# Adafruit_NeoRGB_Stemma_Rev_B.net
KiCad netlist of a schematic drawn in EAGLE
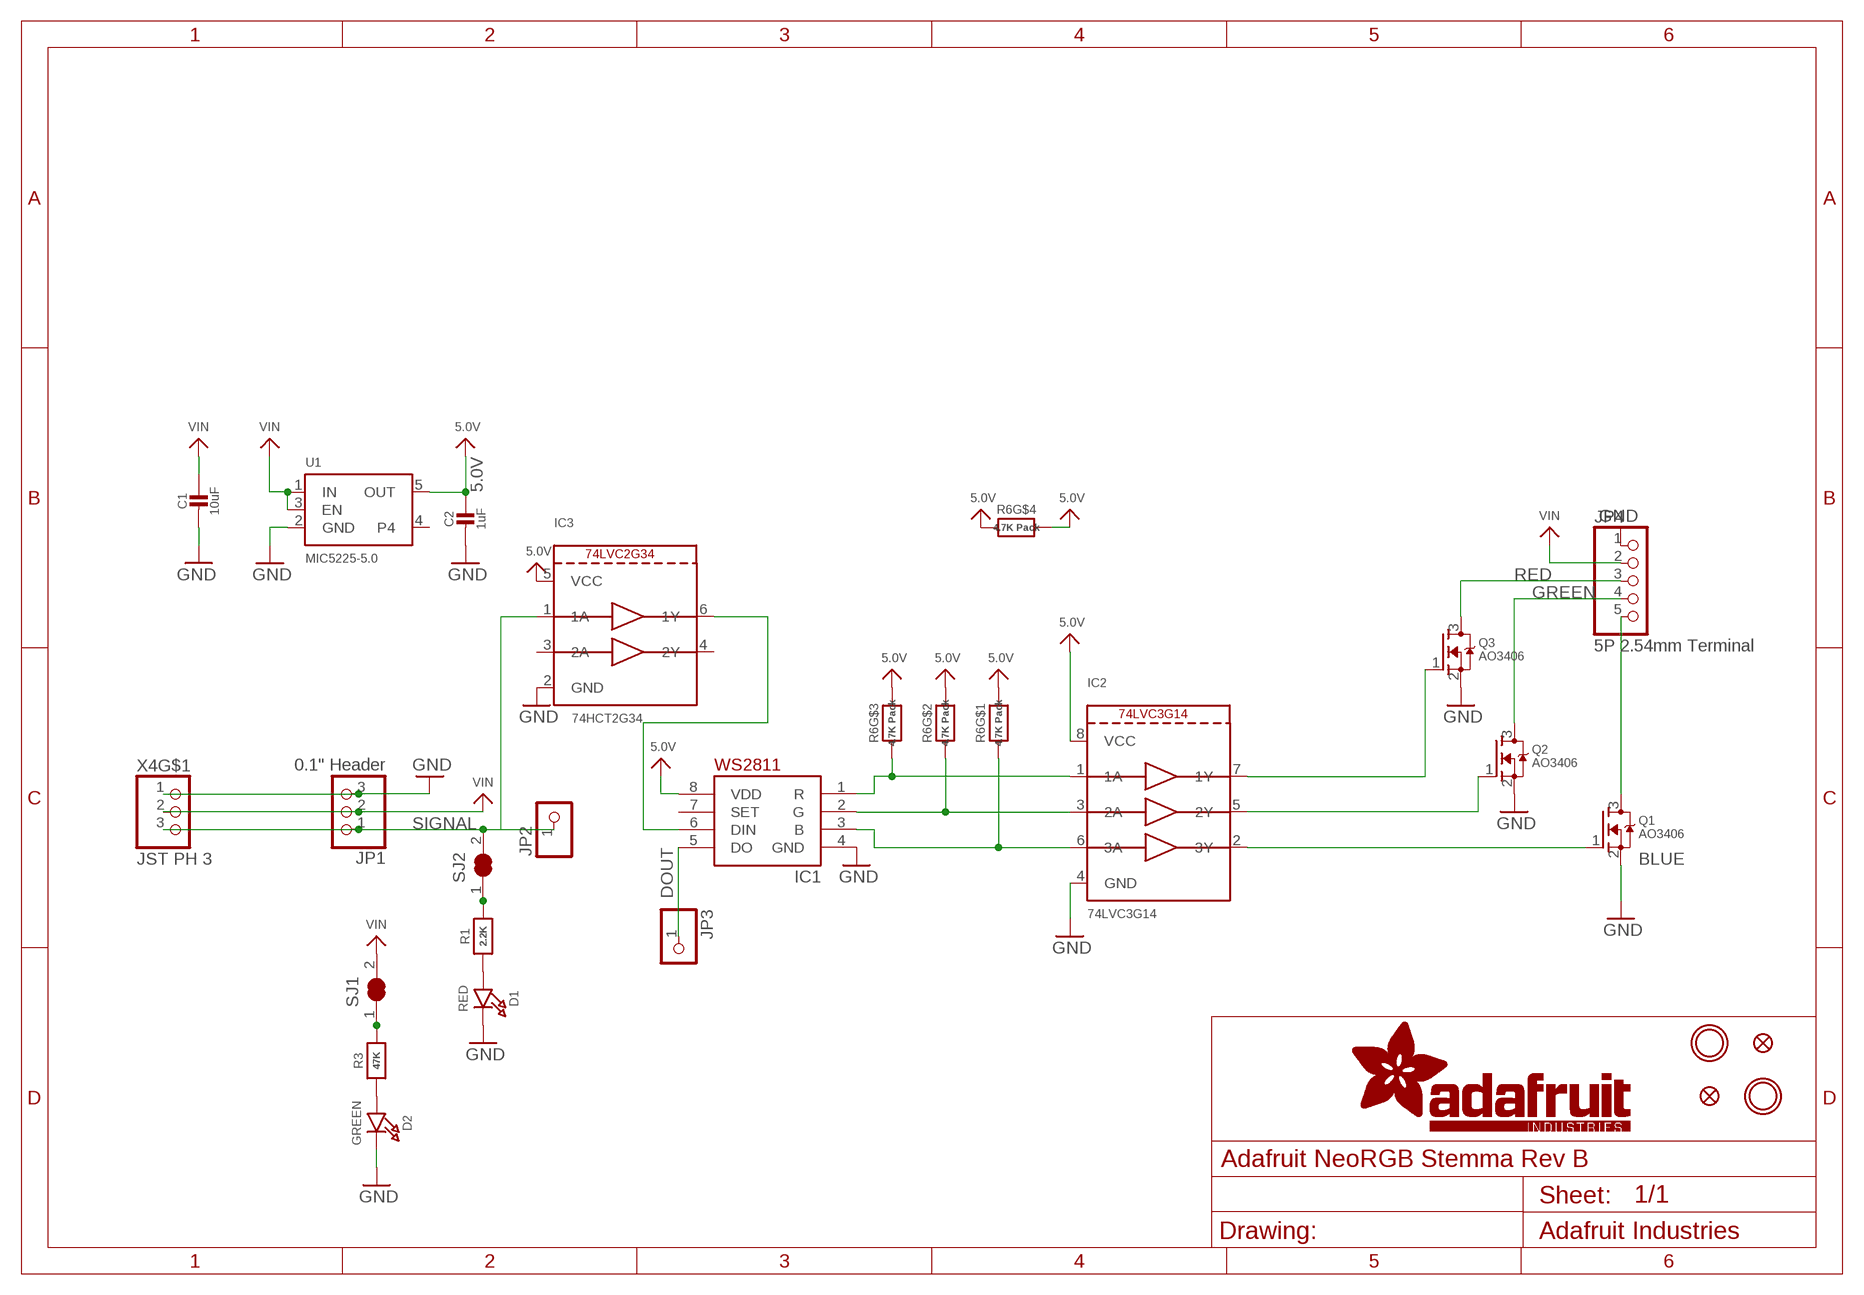
[diagram p0: schematic, sheet 1]

(export (version "E")
  (design (tool "Eeschema 10.0.6"))
  (components
    (comp (ref "C1")
      (value "10uF")
      (footprint "eagle-import:0805-NO")
      (libsource (lib "eagle-import") (part "CAP_CERAMIC0805-NOOUTLINE"))
    )
    (comp (ref "C2")
      (value "1uF")
      (footprint "eagle-import:0603-NO")
      (libsource (lib "eagle-import") (part "CAP_CERAMIC0603_NO"))
    )
    (comp (ref "D1")
      (value "RED")
      (footprint "eagle-import:CHIPLED_0603_NOOUTLINE")
      (libsource (lib "eagle-import") (part "LED0603_NOOUTLINE"))
    )
    (comp (ref "D2")
      (value "GREEN")
      (footprint "eagle-import:CHIPLED_0603_NOOUTLINE")
      (libsource (lib "eagle-import") (part "LED0603_NOOUTLINE"))
    )
    (comp (ref "FID2")
      (value "FIDUCIAL_1MM")
      (footprint "eagle-import:FIDUCIAL_1MM")
      (libsource (lib "eagle-import") (part "FIDUCIAL_1MM"))
    )
    (comp (ref "FID3")
      (value "FIDUCIAL_1MM")
      (footprint "eagle-import:FIDUCIAL_1MM")
      (libsource (lib "eagle-import") (part "FIDUCIAL_1MM"))
    )
    (comp (ref "IC1")
      (value "WS2811F")
      (footprint "eagle-import:FSOP-8")
      (libsource (lib "eagle-import") (part "WS2811F"))
    )
    (comp (ref "IC2")
      (value "74LVC3G14")
      (footprint "eagle-import:VFSOP-8")
      (libsource (lib "eagle-import") (part "74LVC3G14"))
    )
    (comp (ref "IC3")
      (value "74HCT2G34")
      (footprint "eagle-import:SC70-6L")
      (libsource (lib "eagle-import") (part "74LVC2G34"))
    )
    (comp (ref "JP1")
      (value "0.1\" Header")
      (footprint "eagle-import:1X03_OVAL")
      (libsource (lib "eagle-import") (part "HEADER-1X3"))
    )
    (comp (ref "JP2")
      (value "HEADER-1X1ROUND")
      (footprint "eagle-import:1X01_ROUND")
      (libsource (lib "eagle-import") (part "HEADER-1X1ROUND"))
    )
    (comp (ref "JP3")
      (value "HEADER-1X1ROUND")
      (footprint "eagle-import:1X01_ROUND")
      (libsource (lib "eagle-import") (part "HEADER-1X1ROUND"))
    )
    (comp (ref "JP4")
      (value "5P 2.54mm Terminal")
      (footprint "eagle-import:1X05_2.54MMTERMINAL")
      (libsource (lib "eagle-import") (part "HEADER-1X5_2.54MMTERM"))
    )
    (comp (ref "Q1")
      (value "AO3406")
      (footprint "eagle-import:SOT23-WIDE")
      (libsource (lib "eagle-import") (part "MOSFET-NWIDE"))
    )
    (comp (ref "Q2")
      (value "AO3406")
      (footprint "eagle-import:SOT23-WIDE")
      (libsource (lib "eagle-import") (part "MOSFET-NWIDE"))
    )
    (comp (ref "Q3")
      (value "AO3406")
      (footprint "eagle-import:SOT23-WIDE")
      (libsource (lib "eagle-import") (part "MOSFET-NWIDE"))
    )
    (comp (ref "R1")
      (value "2.2K")
      (footprint "eagle-import:0603-NO")
      (libsource (lib "eagle-import") (part "RESISTOR_0603_NOOUT"))
    )
    (comp (ref "R3")
      (value "47K")
      (footprint "eagle-import:0603-NO")
      (libsource (lib "eagle-import") (part "RESISTOR_0603_NOOUT"))
    )
    (comp (ref "R6")
      (value "4.7K Pack")
      (footprint "eagle-import:RESPACK_4X0402")
      (libsource (lib "eagle-import") (part "RESISTOR_4PACK_0804"))
    )
    (comp (ref "SJ1")
      (value "SOLDERJUMPER_CLOSED")
      (footprint "eagle-import:SOLDERJUMPER_CLOSEDWIRE")
      (libsource (lib "eagle-import") (part "SOLDERJUMPER_CLOSED"))
    )
    (comp (ref "SJ2")
      (value "SOLDERJUMPER_CLOSED")
      (footprint "eagle-import:SOLDERJUMPER_CLOSEDWIRE")
      (libsource (lib "eagle-import") (part "SOLDERJUMPER_CLOSED"))
    )
    (comp (ref "U$1")
      (value "MOUNTINGHOLE2.5")
      (footprint "eagle-import:MOUNTINGHOLE_2.5_PLATED")
      (libsource (lib "eagle-import") (part "MOUNTINGHOLE2.5"))
    )
    (comp (ref "U$8")
      (value "MOUNTINGHOLE2.5")
      (footprint "eagle-import:MOUNTINGHOLE_2.5_PLATED")
      (libsource (lib "eagle-import") (part "MOUNTINGHOLE2.5"))
    )
    (comp (ref "U1")
      (value "MIC5225-5.0")
      (footprint "eagle-import:SOT23-5")
      (fields (field (name "JLC_ROTATION") "0"))
      (libsource (lib "eagle-import") (part "VREG_SOT23-5"))
    )
    (comp (ref "X4")
      (value "JST PH 3")
      (footprint "eagle-import:JSTPH3")
      (libsource (lib "eagle-import") (part "CON_JST_PH_3PIN"))
    )
  )
  (nets
    (net (code "1") (name "/BLUE") (class "Default")
      (node (ref "JP4") (pin "5") (pinfunction "5_5") (pintype "passive"))
      (node (ref "Q1") (pin "3") (pinfunction "D_3") (pintype "bidirectional"))
    )
    (net (code "2") (name "/DOUT") (class "Default")
      (node (ref "IC1") (pin "5") (pinfunction "DO_5") (pintype "output"))
      (node (ref "JP3") (pin "1") (pinfunction "1_1") (pintype "passive"))
    )
    (net (code "3") (name "/GREEN") (class "Default")
      (node (ref "JP4") (pin "4") (pinfunction "4_4") (pintype "passive"))
      (node (ref "Q2") (pin "3") (pinfunction "D_3") (pintype "bidirectional"))
    )
    (net (code "4") (name "/RED") (class "Default")
      (node (ref "JP4") (pin "3") (pinfunction "3_3") (pintype "passive"))
      (node (ref "Q3") (pin "3") (pinfunction "D_3") (pintype "bidirectional"))
    )
    (net (code "5") (name "/SIGNAL") (class "Default")
      (node (ref "IC3") (pin "1") (pinfunction "1A_1") (pintype "input"))
      (node (ref "JP1") (pin "1") (pinfunction "1_1") (pintype "passive"))
      (node (ref "JP2") (pin "1") (pinfunction "1_1") (pintype "passive"))
      (node (ref "SJ2") (pin "2") (pinfunction "2_2") (pintype "passive"))
      (node (ref "X4") (pin "3") (pinfunction "3_3") (pintype "passive"))
    )
    (net (code "6") (name "5.0V") (class "Default")
      (node (ref "C2") (pin "1") (pinfunction "1_1") (pintype "passive"))
      (node (ref "IC1") (pin "8") (pinfunction "VDD_8") (pintype "power_in"))
      (node (ref "IC2") (pin "8") (pinfunction "VCC_8") (pintype "power_in"))
      (node (ref "IC3") (pin "5") (pinfunction "VCC_5") (pintype "power_in"))
      (node (ref "R6") (pin "4") (pinfunction "1_4") (pintype "passive"))
      (node (ref "R6") (pin "5") (pinfunction "2_5") (pintype "passive"))
      (node (ref "R6") (pin "6") (pinfunction "2_6") (pintype "passive"))
      (node (ref "R6") (pin "7") (pinfunction "2_7") (pintype "passive"))
      (node (ref "R6") (pin "8") (pinfunction "2_8") (pintype "passive"))
      (node (ref "U1") (pin "5") (pinfunction "OUT_5") (pintype "power_in"))
    )
    (net (code "7") (name "GND") (class "Default")
      (node (ref "C1") (pin "2") (pinfunction "2_2") (pintype "passive"))
      (node (ref "C2") (pin "2") (pinfunction "2_2") (pintype "passive"))
      (node (ref "D1") (pin "C") (pinfunction "C_C") (pintype "passive"))
      (node (ref "D2") (pin "C") (pinfunction "C_C") (pintype "passive"))
      (node (ref "IC1") (pin "4") (pinfunction "GND_4") (pintype "power_in"))
      (node (ref "IC2") (pin "4") (pinfunction "GND_4") (pintype "power_in"))
      (node (ref "IC3") (pin "2") (pinfunction "GND_2") (pintype "power_in"))
      (node (ref "JP1") (pin "3") (pinfunction "3_3") (pintype "passive"))
      (node (ref "JP4") (pin "1") (pinfunction "1_1") (pintype "passive"))
      (node (ref "Q1") (pin "2") (pinfunction "S_2") (pintype "bidirectional"))
      (node (ref "Q2") (pin "2") (pinfunction "S_2") (pintype "bidirectional"))
      (node (ref "Q3") (pin "2") (pinfunction "S_2") (pintype "bidirectional"))
      (node (ref "U1") (pin "2") (pinfunction "GND_2") (pintype "power_in"))
      (node (ref "X4") (pin "1") (pinfunction "1_1") (pintype "passive"))
    )
    (net (code "8") (name "Net-(D1-PadA)") (class "Default")
      (node (ref "D1") (pin "A") (pinfunction "A_A") (pintype "passive"))
      (node (ref "R1") (pin "1") (pinfunction "1_1") (pintype "passive"))
    )
    (net (code "9") (name "Net-(D2-PadA)") (class "Default")
      (node (ref "D2") (pin "A") (pinfunction "A_A") (pintype "passive"))
      (node (ref "R3") (pin "1") (pinfunction "1_1") (pintype "passive"))
    )
    (net (code "10") (name "Net-(IC1-B)") (class "Default")
      (node (ref "IC1") (pin "3") (pinfunction "B_3") (pintype "open_collector"))
      (node (ref "IC2") (pin "6") (pinfunction "3A_6") (pintype "input"))
      (node (ref "R6") (pin "1") (pinfunction "1_1") (pintype "passive"))
    )
    (net (code "11") (name "Net-(IC1-DIN)") (class "Default")
      (node (ref "IC1") (pin "6") (pinfunction "DIN_6") (pintype "input"))
      (node (ref "IC3") (pin "6") (pinfunction "1Y_6") (pintype "output"))
    )
    (net (code "12") (name "Net-(IC1-G)") (class "Default")
      (node (ref "IC1") (pin "2") (pinfunction "G_2") (pintype "open_collector"))
      (node (ref "IC2") (pin "3") (pinfunction "2A_3") (pintype "input"))
      (node (ref "R6") (pin "2") (pinfunction "1_2") (pintype "passive"))
    )
    (net (code "13") (name "Net-(IC1-R)") (class "Default")
      (node (ref "IC1") (pin "1") (pinfunction "R_1") (pintype "open_collector"))
      (node (ref "IC2") (pin "1") (pinfunction "1A_1") (pintype "input"))
      (node (ref "R6") (pin "3") (pinfunction "1_3") (pintype "passive"))
    )
    (net (code "14") (name "Net-(IC2-1Y)") (class "Default")
      (node (ref "IC2") (pin "7") (pinfunction "1Y_7") (pintype "output"))
      (node (ref "Q3") (pin "1") (pinfunction "G_1") (pintype "bidirectional"))
    )
    (net (code "15") (name "Net-(IC2-2Y)") (class "Default")
      (node (ref "IC2") (pin "5") (pinfunction "2Y_5") (pintype "output"))
      (node (ref "Q2") (pin "1") (pinfunction "G_1") (pintype "bidirectional"))
    )
    (net (code "16") (name "Net-(IC2-3Y)") (class "Default")
      (node (ref "IC2") (pin "2") (pinfunction "3Y_2") (pintype "output"))
      (node (ref "Q1") (pin "1") (pinfunction "G_1") (pintype "bidirectional"))
    )
    (net (code "17") (name "Net-(R1-Pad2)") (class "Default")
      (node (ref "R1") (pin "2") (pinfunction "2_2") (pintype "passive"))
      (node (ref "SJ2") (pin "1") (pinfunction "1_1") (pintype "passive"))
    )
    (net (code "18") (name "Net-(R3-Pad2)") (class "Default")
      (node (ref "R3") (pin "2") (pinfunction "2_2") (pintype "passive"))
      (node (ref "SJ1") (pin "1") (pinfunction "1_1") (pintype "passive"))
    )
    (net (code "19") (name "VIN") (class "Default")
      (node (ref "C1") (pin "1") (pinfunction "1_1") (pintype "passive"))
      (node (ref "JP1") (pin "2") (pinfunction "2_2") (pintype "passive"))
      (node (ref "JP4") (pin "2") (pinfunction "2_2") (pintype "passive"))
      (node (ref "SJ1") (pin "2") (pinfunction "2_2") (pintype "passive"))
      (node (ref "U1") (pin "1") (pinfunction "IN_1") (pintype "power_in"))
      (node (ref "U1") (pin "3") (pinfunction "EN_3") (pintype "input"))
      (node (ref "X4") (pin "2") (pinfunction "2_2") (pintype "passive"))
    )
    (net (code "20") (name "unconnected-(IC1-SET-Pad7)") (class "Default")
      (node (ref "IC1") (pin "7") (pinfunction "SET_7") (pintype "input"))
    )
    (net (code "21") (name "unconnected-(IC3-2A-Pad3)") (class "Default")
      (node (ref "IC3") (pin "3") (pinfunction "2A_3") (pintype "input"))
    )
    (net (code "22") (name "unconnected-(IC3-2Y-Pad4)") (class "Default")
      (node (ref "IC3") (pin "4") (pinfunction "2Y_4") (pintype "output"))
    )
    (net (code "23") (name "unconnected-(U1-P4-Pad4)") (class "Default")
      (node (ref "U1") (pin "4") (pinfunction "P4_4") (pintype "bidirectional"))
    )
  )
)
